# tick-ds3231-breakout-mk-2_0.net
KiCad netlist of a schematic drawn in EAGLE
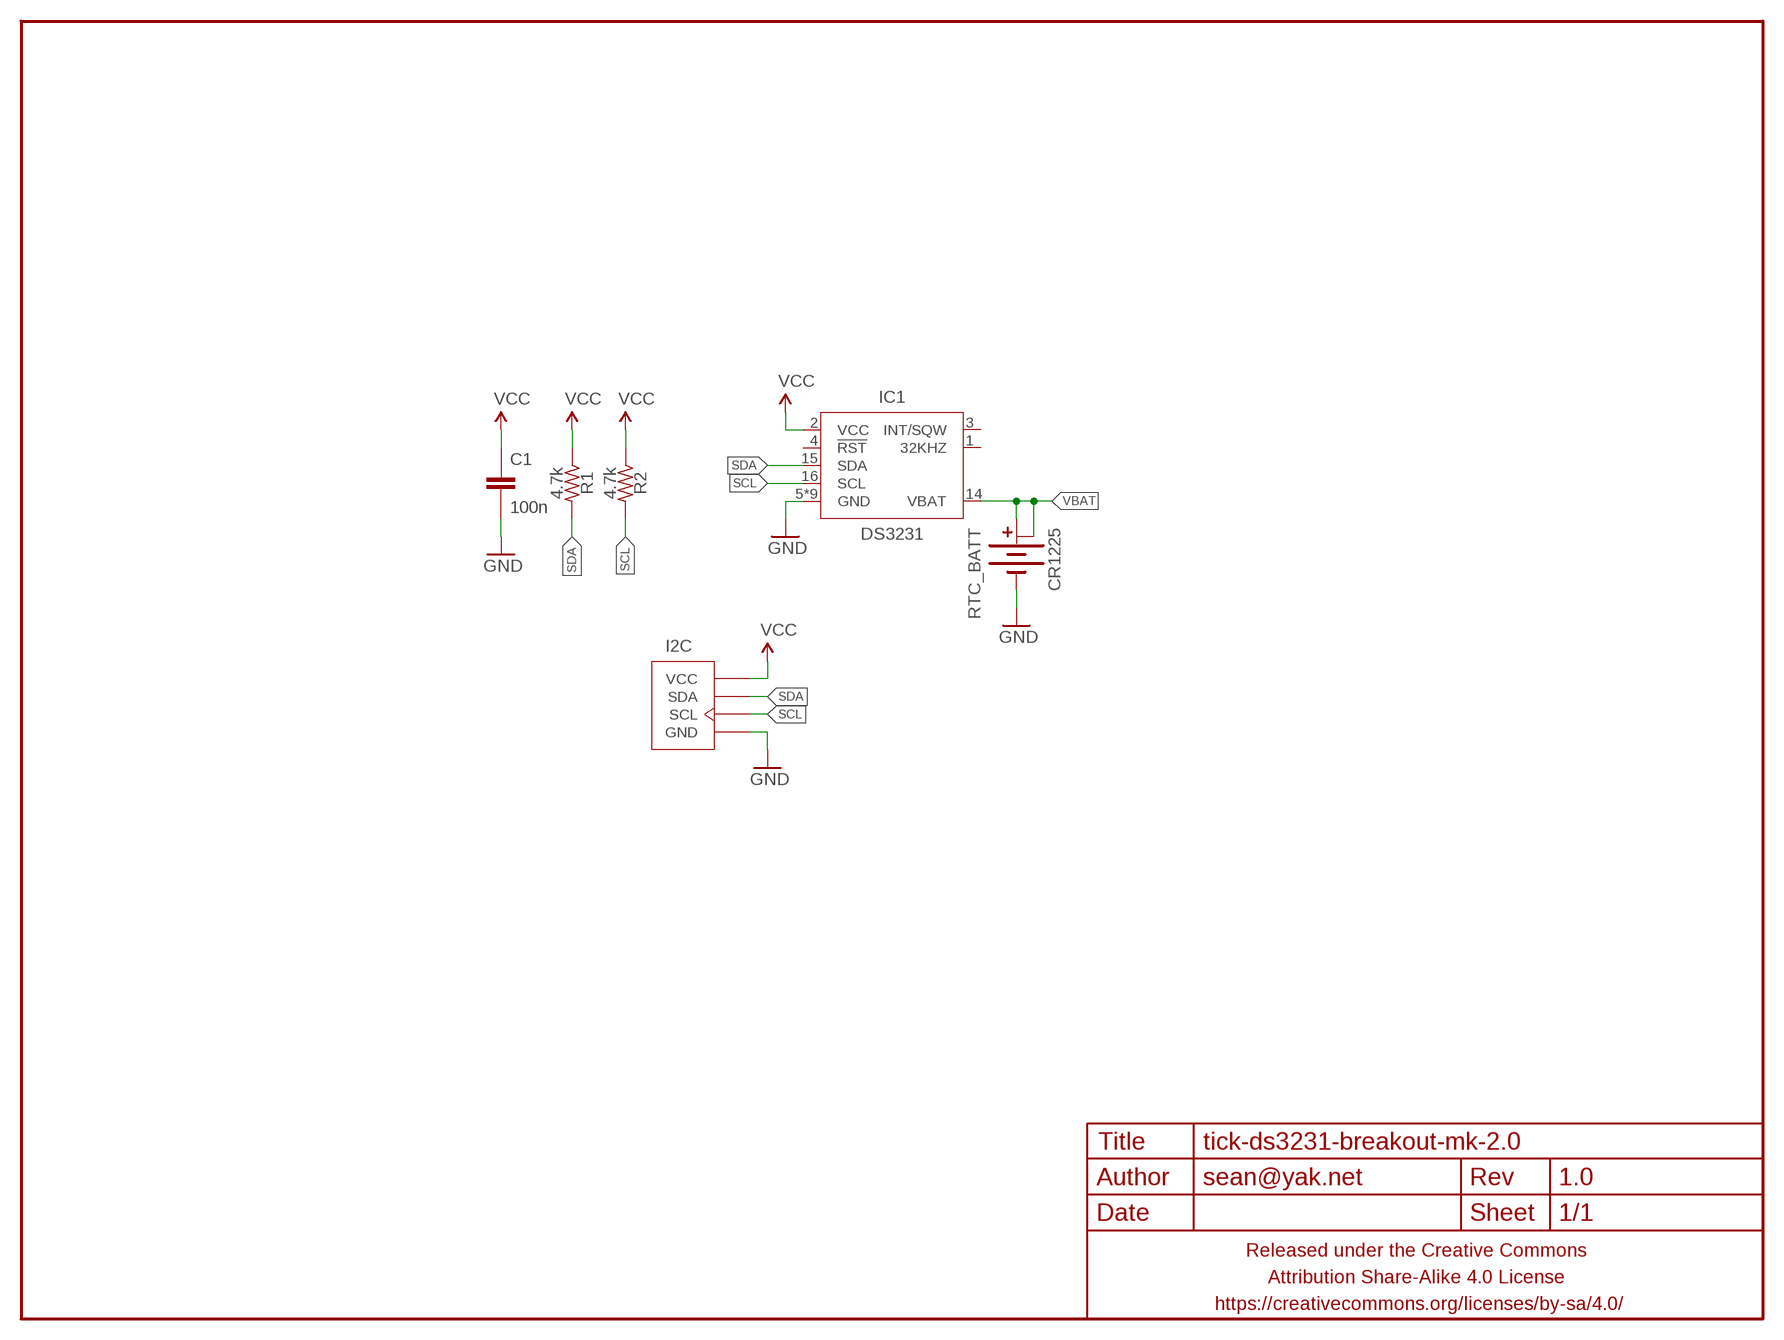
[diagram p0: schematic, sheet 1]

(export (version "E")
  (design (tool "Eeschema 10.0.6"))
  (components
    (comp (ref "C1")
      (value "100n")
      (footprint "eagle-import:C0805")
      (libsource (lib "eagle-import") (part "CAPACITOR-CERAMICC0805"))
    )
    (comp (ref "FRAME1")
      (value "FRAME-LETTERNO_PACKAGE")
      (footprint "eagle-import:DUMMY")
      (fields (field (name "DESIGNER") "sean@yak.net") (field (name "VERSION") "1.0"))
      (libsource (lib "eagle-import") (part "FRAME-LETTERNO_PACKAGE"))
    )
    (comp (ref "I2C")
      (value "M04-I2CPTH-0.1IN-CENTERED")
      (footprint "eagle-import:1X04-PTH-VERT-I2C-CENTERED")
      (libsource (lib "eagle-import") (part "M04-I2CPTH-0.1IN-CENTERED"))
    )
    (comp (ref "IC1")
      (value "DS3231")
      (footprint "eagle-import:SO16W")
      (libsource (lib "eagle-import") (part "DS3231"))
    )
    (comp (ref "R1")
      (value "4.7k")
      (footprint "eagle-import:R0805")
      (libsource (lib "eagle-import") (part "RESISTORR0805"))
    )
    (comp (ref "R2")
      (value "4.7k")
      (footprint "eagle-import:R0805")
      (libsource (lib "eagle-import") (part "RESISTORR0805"))
    )
    (comp (ref "RTC_BATT")
      (value "CR1225")
      (footprint "eagle-import:BATTCON_12MM_SMD")
      (libsource (lib "eagle-import") (part "BATTERY-COINCR1225_SMD_SMALLER"))
    )
  )
  (nets
    (net (code "1") (name "GND") (class "Default")
      (node (ref "C1") (pin "2") (pinfunction "2_2") (pintype "passive"))
      (node (ref "I2C") (pin "GND") (pinfunction "GND_GND") (pintype "bidirectional"))
      (node (ref "IC1") (pin "10") (pinfunction "GND_10") (pintype "bidirectional"))
      (node (ref "IC1") (pin "11") (pinfunction "GND_11") (pintype "bidirectional"))
      (node (ref "IC1") (pin "12") (pinfunction "GND_12") (pintype "bidirectional"))
      (node (ref "IC1") (pin "13") (pinfunction "GND_13") (pintype "bidirectional"))
      (node (ref "IC1") (pin "5") (pinfunction "GND_5") (pintype "bidirectional"))
      (node (ref "IC1") (pin "6") (pinfunction "GND_6") (pintype "bidirectional"))
      (node (ref "IC1") (pin "7") (pinfunction "GND_7") (pintype "bidirectional"))
      (node (ref "IC1") (pin "8") (pinfunction "GND_8") (pintype "bidirectional"))
      (node (ref "IC1") (pin "9") (pinfunction "GND_9") (pintype "bidirectional"))
      (node (ref "RTC_BATT") (pin "-") (pinfunction "-_-") (pintype "bidirectional"))
    )
    (net (code "2") (name "SCL") (class "Default")
      (node (ref "I2C") (pin "SCL") (pinfunction "SCL_SCL") (pintype "bidirectional"))
      (node (ref "IC1") (pin "16") (pinfunction "SCL_16") (pintype "bidirectional"))
      (node (ref "R2") (pin "2") (pinfunction "2_2") (pintype "passive"))
    )
    (net (code "3") (name "SDA") (class "Default")
      (node (ref "I2C") (pin "SDA") (pinfunction "SDA_SDA") (pintype "bidirectional"))
      (node (ref "IC1") (pin "15") (pinfunction "SDA_15") (pintype "bidirectional"))
      (node (ref "R1") (pin "2") (pinfunction "2_2") (pintype "passive"))
    )
    (net (code "4") (name "VBAT") (class "Default")
      (node (ref "IC1") (pin "14") (pinfunction "VBAT_14") (pintype "bidirectional"))
      (node (ref "RTC_BATT") (pin "+@1") (pinfunction "+_+@1") (pintype "bidirectional"))
      (node (ref "RTC_BATT") (pin "+@2") (pinfunction "+1_+@2") (pintype "bidirectional"))
    )
    (net (code "5") (name "VCC") (class "Default")
      (node (ref "C1") (pin "1") (pinfunction "1_1") (pintype "passive"))
      (node (ref "I2C") (pin "VCC") (pinfunction "VCC_VCC") (pintype "bidirectional"))
      (node (ref "IC1") (pin "2") (pinfunction "VCC_2") (pintype "bidirectional"))
      (node (ref "R1") (pin "1") (pinfunction "1_1") (pintype "passive"))
      (node (ref "R2") (pin "1") (pinfunction "1_1") (pintype "passive"))
    )
    (net (code "6") (name "unconnected-(IC1-32KHZ-Pad1)") (class "Default")
      (node (ref "IC1") (pin "1") (pinfunction "32KHZ_1") (pintype "bidirectional"))
    )
    (net (code "7") (name "unconnected-(IC1-INT{slash}SQW-Pad3)") (class "Default")
      (node (ref "IC1") (pin "3") (pinfunction "INT/SQW_3") (pintype "bidirectional"))
    )
    (net (code "8") (name "unconnected-(IC1-~{RST}-Pad4)") (class "Default")
      (node (ref "IC1") (pin "4") (pinfunction "~{RST}_4") (pintype "bidirectional"))
    )
  )
)
